# FMU_Power_FMU_REV_1A.net
KiCad netlist of a schematic drawn in Altium Designer
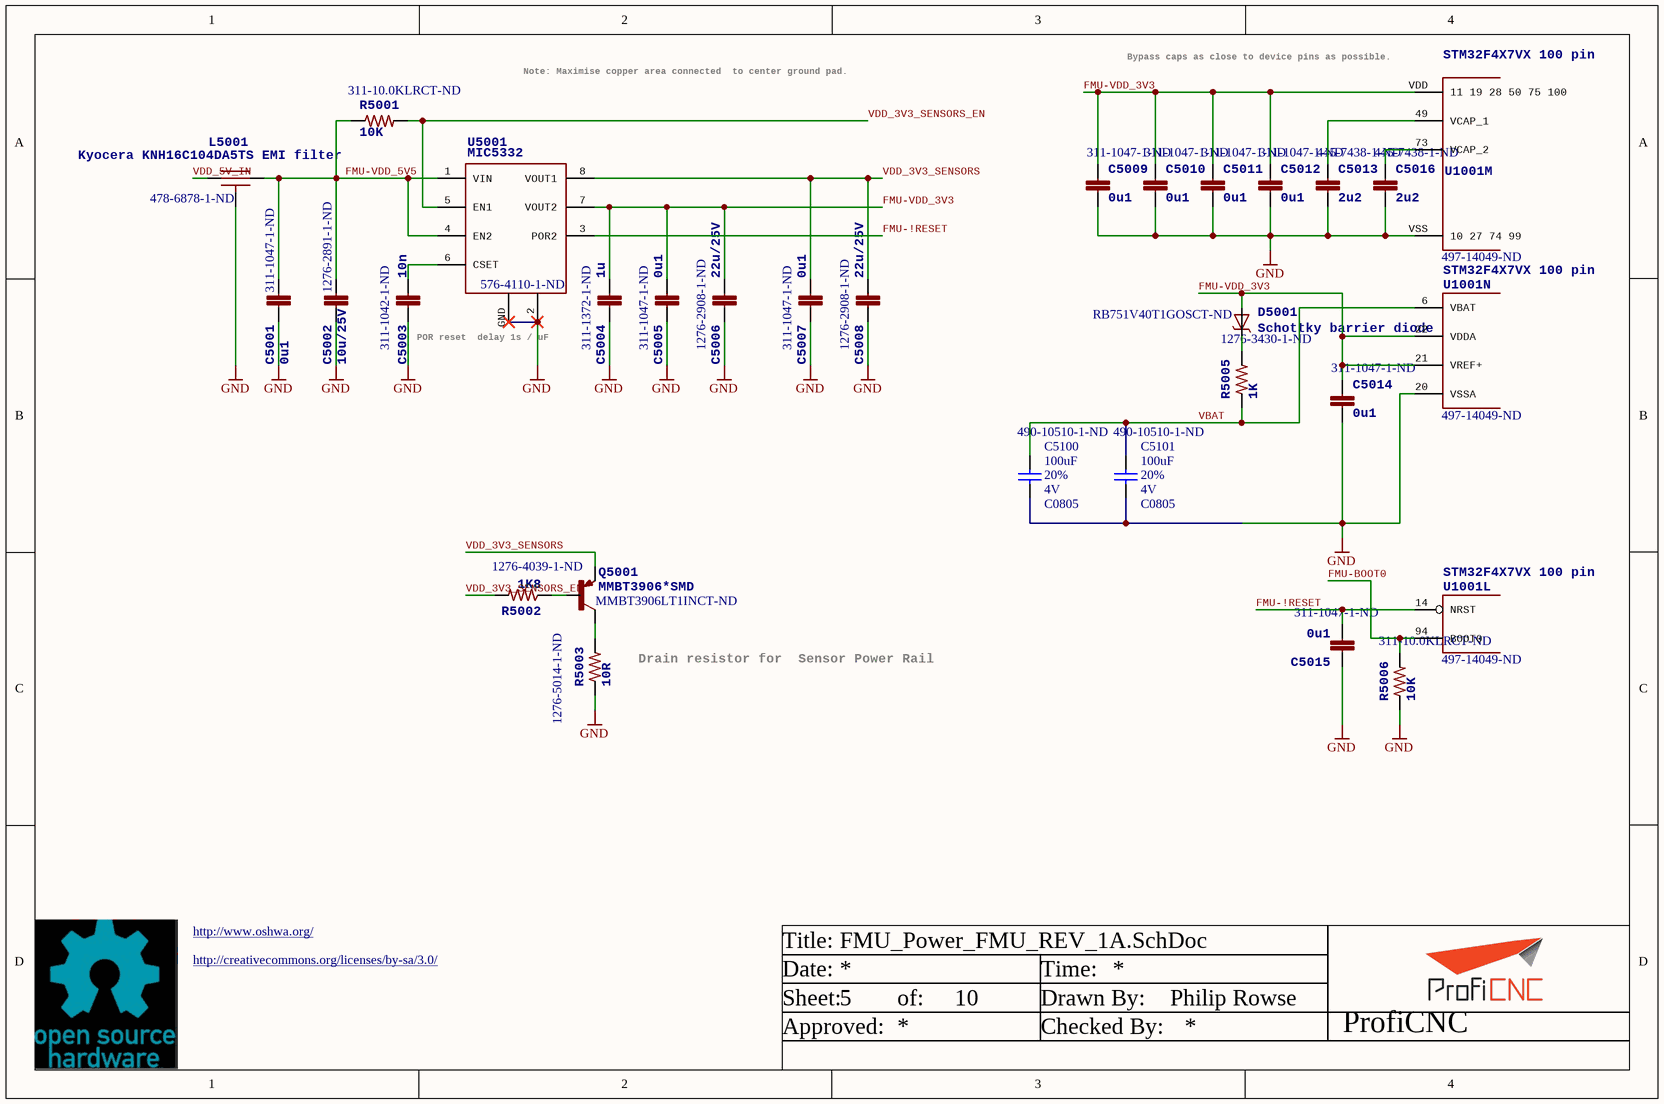
[diagram p0: FMU_Power_FMU_REV_1A.SchDoc]

(export (version "E")
  (design (tool "Eeschema 10.0.6"))
  (components
    (comp (ref "C5001")
      (value "0u1")
      (footprint "0402-CAP")
      (description "CAP CER 0.1UF 16V Y5V 0402")
      (fields
        (field (name "PARTNO") "CC0402ZRY5V7BB104")
        (field (name "SUPPLIER PART NUMBER 1") "311-1047-1-ND")
        (field (name "3DR_PARTNO") "ECM0700")
      )
      (libsource (lib "pixhawk2") (part "CAP0402"))
    )
    (comp (ref "C5002")
      (value "10u/25V")
      (footprint "0805-CAP")
      (description "CAP CER 10UF 25V 10% X5R 0805")
      (fields
        (field (name "PARTNO") "CL21A106KAYNNNE")
        (field (name "SUPPLIER PART NUMBER 1") "1276-2891-1-ND")
        (field (name "3DR_PARTNO") "ECM0714")
      )
      (libsource (lib "pixhawk2") (part "CAP0805"))
    )
    (comp (ref "C5003")
      (value "10n")
      (footprint "0402-CAP")
      (description "CAP CER 10000PF 16V 10% X7R 0402")
      (fields
        (field (name "PARTNO") "CC0402KRX7R7BB103")
        (field (name "SUPPLIER PART NUMBER 1") "311-1042-1-ND")
        (field (name "3DR_PARTNO") "ECM0711")
      )
      (libsource (lib "") (part "CAP0402_1"))
    )
    (comp (ref "C5004")
      (value "1u")
      (footprint "0603-CAP")
      (description "CAP CER 1UF 16V Y5V 0603")
      (fields
        (field (name "PARTNO") "CC0603ZRY5V7BB105")
        (field (name "SUPPLIER PART NUMBER 1") "311-1372-1-ND")
        (field (name "3DR_PARTNO") "ECM0705")
      )
      (libsource (lib "pixhawk2") (part "CAP0603"))
    )
    (comp (ref "C5005")
      (value "0u1")
      (footprint "0402-CAP")
      (description "CAP CER 0.1UF 16V Y5V 0402")
      (fields
        (field (name "PARTNO") "CC0402ZRY5V7BB104")
        (field (name "SUPPLIER PART NUMBER 1") "311-1047-1-ND")
        (field (name "3DR_PARTNO") "ECM0700")
      )
      (libsource (lib "pixhawk2") (part "CAP0402"))
    )
    (comp (ref "C5006")
      (value "22u/25V")
      (footprint "0805-CAP")
      (description "CAP CER 22UF 25V 20% X5R 0805")
      (fields
        (field (name "PARTNO") "CL21A226MAQNNNE")
        (field (name "SUPPLIER PART NUMBER 1") "1276-2908-1-ND")
        (field (name "3DR_PARTNO") "ECM0715")
      )
      (libsource (lib "pixhawk2") (part "CAP0805"))
    )
    (comp (ref "C5007")
      (value "0u1")
      (footprint "0402-CAP")
      (description "CAP CER 0.1UF 16V Y5V 0402")
      (fields
        (field (name "PARTNO") "CC0402ZRY5V7BB104")
        (field (name "SUPPLIER PART NUMBER 1") "311-1047-1-ND")
        (field (name "3DR_PARTNO") "ECM0700")
      )
      (libsource (lib "pixhawk2") (part "CAP0402"))
    )
    (comp (ref "C5008")
      (value "22u/25V")
      (footprint "0805-CAP")
      (description "CAP CER 22UF 25V 20% X5R 0805")
      (fields
        (field (name "PARTNO") "CL21A226MAQNNNE")
        (field (name "SUPPLIER PART NUMBER 1") "1276-2908-1-ND")
        (field (name "3DR_PARTNO") "ECM0715")
      )
      (libsource (lib "pixhawk2") (part "CAP0805"))
    )
    (comp (ref "C5009")
      (value "0u1")
      (footprint "0402-CAP")
      (description "CAP CER 0.1UF 16V Y5V 0402")
      (fields
        (field (name "PARTNO") "CC0402ZRY5V7BB104")
        (field (name "SUPPLIER PART NUMBER 1") "311-1047-1-ND")
        (field (name "3DR_PARTNO") "ECM0700")
      )
      (libsource (lib "pixhawk2") (part "CAP0402"))
    )
    (comp (ref "C5010")
      (value "0u1")
      (footprint "0402-CAP")
      (description "CAP CER 0.1UF 16V Y5V 0402")
      (fields
        (field (name "PARTNO") "CC0402ZRY5V7BB104")
        (field (name "SUPPLIER PART NUMBER 1") "311-1047-1-ND")
        (field (name "3DR_PARTNO") "ECM0700")
      )
      (libsource (lib "pixhawk2") (part "CAP0402"))
    )
    (comp (ref "C5011")
      (value "0u1")
      (footprint "0402-CAP")
      (description "CAP CER 0.1UF 16V Y5V 0402")
      (fields
        (field (name "PARTNO") "CC0402ZRY5V7BB104")
        (field (name "SUPPLIER PART NUMBER 1") "311-1047-1-ND")
        (field (name "3DR_PARTNO") "ECM0700")
      )
      (libsource (lib "pixhawk2") (part "CAP0402"))
    )
    (comp (ref "C5012")
      (value "0u1")
      (footprint "0402-CAP")
      (description "CAP CER 0.1UF 16V Y5V 0402")
      (fields
        (field (name "PARTNO") "CC0402ZRY5V7BB104")
        (field (name "SUPPLIER PART NUMBER 1") "311-1047-1-ND")
        (field (name "3DR_PARTNO") "ECM0700")
      )
      (libsource (lib "pixhawk2") (part "CAP0402"))
    )
    (comp (ref "C5013")
      (value "2u2")
      (footprint "0603-CAP")
      (description "CAP CER 2.2UF 16V 10% X6S 0603")
      (fields
        (field (name "PARTNO") "C1608X6S1C225K080AC")
        (field (name "SUPPLIER PART NUMBER 1") "445-7438-1-ND")
        (field (name "3DR_PARTNO") "ECM0619")
      )
      (libsource (lib "pixhawk2") (part "CAP0603"))
    )
    (comp (ref "C5014")
      (value "0u1")
      (footprint "0402-CAP")
      (description "CAP CER 0.1UF 16V Y5V 0402")
      (fields
        (field (name "PARTNO") "CC0402ZRY5V7BB104")
        (field (name "SUPPLIER PART NUMBER 1") "311-1047-1-ND")
        (field (name "3DR_PARTNO") "ECM0700")
      )
      (libsource (lib "pixhawk2") (part "CAP0402"))
    )
    (comp (ref "C5015")
      (value "0u1")
      (footprint "0402-CAP")
      (description "CAP CER 0.1UF 16V Y5V 0402")
      (fields
        (field (name "PARTNO") "CC0402ZRY5V7BB104")
        (field (name "SUPPLIER PART NUMBER 1") "311-1047-1-ND")
        (field (name "3DR_PARTNO") "ECM0700")
      )
      (libsource (lib "") (part "CAP0402_2"))
    )
    (comp (ref "C5016")
      (value "2u2")
      (footprint "0603-CAP")
      (description "CAP CER 2.2UF 16V 10% X6S 0603")
      (fields
        (field (name "PARTNO") "C1608X6S1C225K080AC")
        (field (name "SUPPLIER PART NUMBER 1") "445-7438-1-ND")
        (field (name "3DR_PARTNO") "ECM0619")
      )
      (libsource (lib "pixhawk2") (part "CAP0603"))
    )
    (comp (ref "C5100")
      (value "100uF")
      (footprint "C0805")
      (fields
        (field (name "TOLERANCE") "20%")
        (field (name "VOLTAGE") "4V")
        (field (name "SUPPLIER PART NUMBER 1") "490-10510-1-ND")
        (field (name "Comment") "GRM21BR60G107ME15L")
      )
      (libsource (lib "3DR") (part "Capacitor"))
    )
    (comp (ref "C5101")
      (value "100uF")
      (footprint "C0805")
      (fields
        (field (name "TOLERANCE") "20%")
        (field (name "VOLTAGE") "4V")
        (field (name "SUPPLIER PART NUMBER 1") "490-10510-1-ND")
        (field (name "Comment") "GRM21BR60G107ME15L")
      )
      (libsource (lib "3DR") (part "Capacitor"))
    )
    (comp (ref "D5001")
      (value "Schottky barrier diode")
      (footprint "SOD323")
      (description "DIODE SCHOTTKY 30V 0.03A SOD323")
      (fields
        (field (name "SUPPLIER PART NUMBER 1") "RB751V40T1GOSCT-ND")
        (field (name "3DR_PARTNO") "ECM0839")
        (field (name "PARTNO") "RB751V40T1G")
      )
      (libsource (lib "pixhawk2") (part "DIODE-SCHOTTKY_SOD323"))
    )
    (comp (ref "L5001")
      (value "Kyocera KNH16C104DA5TS EMI filter")
      (footprint "KYOCERA-KNH16-DA")
      (description "FILTER CAP 0.1UF 2A 25V 0603")
      (fields
        (field (name "SUPPLIER PART NUMBER 1") "478-6878-1-ND")
        (field (name "3DR_PARTNO") "ECM0719")
        (field (name "PARTNO") "KNH16C104DA5TS")
      )
      (libsource (lib "pixhawk2") (part "KNH16C104DA5TS"))
    )
    (comp (ref "Q5001")
      (value "MMBT3906*SMD")
      (footprint "SOT23-BEC")
      (description "TRANSISTOR SWITCHING PNP SOT-23")
      (fields
        (field (name "SUPPLIER PART NUMBER 1") "MMBT3906LT1INCT-ND")
        (field (name "3DR_PARTNO") "ECM0833")
        (field (name "PARTNO") "MMBT 3906 LT1")
      )
      (libsource (lib "transistor-pnp") (part "MMBT3906*SMD"))
    )
    (comp (ref "R5001")
      (value "10K")
      (footprint "0402-RES")
      (description "RES 10K OHM 1/16W 1% 0402 SMD")
      (fields
        (field (name "PARTNO") "RC0402FR-0710KL")
        (field (name "SUPPLIER PART NUMBER 1") "311-10.0KLRCT-ND")
        (field (name "3DR_PARTNO") "ECM0800")
      )
      (libsource (lib "pixhawk2") (part "RESISTOR0402-RES"))
    )
    (comp (ref "R5002")
      (value "1K8")
      (footprint "0402-RES")
      (description "RES 1.8K OHM 1/16W 1% 0402")
      (fields
        (field (name "PARTNO") "RC1005F182CS")
        (field (name "SUPPLIER PART NUMBER 1") "1276-4039-1-ND")
        (field (name "3DR_PARTNO") "ECM0807")
      )
      (libsource (lib "pixhawk2") (part "RESISTOR0402-RES"))
    )
    (comp (ref "R5003")
      (value "10R")
      (footprint "0603-RES")
      (description "RES 10 OHM 1/10W 5% 0603")
      (fields
        (field (name "PARTNO") "RC1608J100CS")
        (field (name "SUPPLIER PART NUMBER 1") "1276-5014-1-ND")
        (field (name "3DR_PARTNO") "ECM0811")
      )
      (libsource (lib "pixhawk2") (part "RESISTOR0603-RES"))
    )
    (comp (ref "R5005")
      (value "1K")
      (footprint "0402-RES")
      (description "RES 1K OHM 1/16W 1% 0402")
      (fields
        (field (name "PARTNO") "RC1005F102CS")
        (field (name "SUPPLIER PART NUMBER 1") "1276-3430-1-ND")
        (field (name "3DR_PARTNO") "ECM0804")
      )
      (libsource (lib "pixhawk2") (part "RESISTOR0402-RES"))
    )
    (comp (ref "R5006")
      (value "10K")
      (footprint "0402-RES")
      (description "RES 10K OHM 1/16W 1% 0402 SMD")
      (fields
        (field (name "PARTNO") "RC0402FR-0710KL")
        (field (name "SUPPLIER PART NUMBER 1") "311-10.0KLRCT-ND")
        (field (name "3DR_PARTNO") "ECM0800")
      )
      (libsource (lib "pixhawk2") (part "RESISTOR0402-RES"))
    )
    (comp (ref "U1001")
      (value "STM32F4X7VX 100 pin")
      (footprint "TQFP100")
      (description "REV 3 Silicon or later IC MCU ARM 2MB FLASH 100LQFP")
      (fields (field (name "SUPPLIER PART NUMBER 1") "497-14049-ND") (field (name "3DR_PARTNO") "ECM0841"))
      (libsource (lib "pixhawk2") (part "STM32F4X7VX"))
    )
    (comp (ref "U5001")
      (value "MIC5332")
      (footprint "MLF-8-EPAD")
      (description "IC REG LDO 3.3V 0.3A 8TMLF")
      (fields
        (field (name "SUPPLIER PART NUMBER 1") "576-4110-1-ND")
        (field (name "3DR_PARTNO") "ECM0832")
        (field (name "PARTNO") "MIC5332-SSYMT TR")
      )
      (libsource (lib "pixhawk2") (part "MIC5332"))
    )
  )
  (nets
    (net (code "1") (name "/FMU-!RESET") (class "Default")
      (node (ref "C5015") (pin "P$2") (pinfunction "2_P$2") (pintype "passive"))
      (node (ref "U1001") (pin "14") (pinfunction "NRST_14") (pintype "passive"))
      (node (ref "U5001") (pin "3") (pinfunction "POR2_3") (pintype "passive"))
    )
    (net (code "2") (name "/FMU-BOOT0") (class "Default")
      (node (ref "R5006") (pin "P$2") (pinfunction "2_P$2") (pintype "passive"))
      (node (ref "U1001") (pin "94") (pinfunction "BOOT0_94") (pintype "passive"))
    )
    (net (code "3") (name "/FMU-VDD_3V3") (class "Default")
      (node (ref "C5004") (pin "P$1") (pinfunction "1_P$1") (pintype "passive"))
      (node (ref "C5005") (pin "P$1") (pinfunction "1_P$1") (pintype "passive"))
      (node (ref "C5006") (pin "P$1") (pinfunction "1_P$1") (pintype "passive"))
      (node (ref "C5009") (pin "P$1") (pinfunction "1_P$1") (pintype "passive"))
      (node (ref "C5010") (pin "P$1") (pinfunction "1_P$1") (pintype "passive"))
      (node (ref "C5011") (pin "P$1") (pinfunction "1_P$1") (pintype "passive"))
      (node (ref "C5012") (pin "P$1") (pinfunction "1_P$1") (pintype "passive"))
      (node (ref "C5014") (pin "P$1") (pinfunction "1_P$1") (pintype "passive"))
      (node (ref "D5001") (pin "A") (pinfunction "A_A") (pintype "passive"))
      (node (ref "U1001") (pin "21") (pinfunction "VREF+_21") (pintype "passive"))
      (node (ref "U1001") (pin "22") (pinfunction "VDDA_22") (pintype "power_in"))
      (node (ref "U1001") (pin "VDD") (pinfunction "11_19_28_50_75_100_VDD") (pintype "power_in"))
      (node (ref "U5001") (pin "7") (pinfunction "VOUT2_7") (pintype "passive"))
    )
    (net (code "4") (name "/FMU-VDD_5V5") (class "Default")
      (node (ref "C5001") (pin "P$1") (pinfunction "1_P$1") (pintype "passive"))
      (node (ref "C5002") (pin "P$1") (pinfunction "1_P$1") (pintype "passive"))
      (node (ref "L5001") (pin "P$2") (pinfunction "P$2_P$2") (pintype "passive"))
      (node (ref "R5001") (pin "P$1") (pinfunction "1_P$1") (pintype "passive"))
      (node (ref "U5001") (pin "1") (pinfunction "VIN_1") (pintype "passive"))
      (node (ref "U5001") (pin "4") (pinfunction "EN2_4") (pintype "passive"))
    )
    (net (code "5") (name "/VBAT") (class "Default")
      (node (ref "C5100") (pin "2") (pinfunction "2_2") (pintype "passive"))
      (node (ref "C5101") (pin "2") (pinfunction "2_2") (pintype "passive"))
      (node (ref "R5005") (pin "P$1") (pinfunction "1_P$1") (pintype "passive"))
      (node (ref "U1001") (pin "6") (pinfunction "VBAT_6") (pintype "power_in"))
    )
    (net (code "6") (name "/VDD_3V3_SENSORS") (class "Default")
      (node (ref "C5007") (pin "P$1") (pinfunction "1_P$1") (pintype "passive"))
      (node (ref "C5008") (pin "P$1") (pinfunction "1_P$1") (pintype "passive"))
      (node (ref "Q5001") (pin "E") (pinfunction "E_E") (pintype "passive"))
      (node (ref "U5001") (pin "8") (pinfunction "VOUT1_8") (pintype "passive"))
    )
    (net (code "7") (name "/VDD_3V3_SENSORS_EN") (class "Default")
      (node (ref "R5001") (pin "P$2") (pinfunction "2_P$2") (pintype "passive"))
      (node (ref "R5002") (pin "P$2") (pinfunction "2_P$2") (pintype "passive"))
      (node (ref "U5001") (pin "5") (pinfunction "EN1_5") (pintype "passive"))
    )
    (net (code "8") (name "/VDD_5V_IN") (class "Default")
      (node (ref "L5001") (pin "P$1") (pinfunction "P$1_P$1") (pintype "passive"))
    )
    (net (code "9") (name "GND") (class "Default")
      (node (ref "C5001") (pin "P$2") (pinfunction "2_P$2") (pintype "passive"))
      (node (ref "C5002") (pin "P$2") (pinfunction "2_P$2") (pintype "passive"))
      (node (ref "C5003") (pin "P$1") (pinfunction "1_P$1") (pintype "passive"))
      (node (ref "C5004") (pin "P$2") (pinfunction "2_P$2") (pintype "passive"))
      (node (ref "C5005") (pin "P$2") (pinfunction "2_P$2") (pintype "passive"))
      (node (ref "C5006") (pin "P$2") (pinfunction "2_P$2") (pintype "passive"))
      (node (ref "C5007") (pin "P$2") (pinfunction "2_P$2") (pintype "passive"))
      (node (ref "C5008") (pin "P$2") (pinfunction "2_P$2") (pintype "passive"))
      (node (ref "C5009") (pin "P$2") (pinfunction "2_P$2") (pintype "passive"))
      (node (ref "C5010") (pin "P$2") (pinfunction "2_P$2") (pintype "passive"))
      (node (ref "C5011") (pin "P$2") (pinfunction "2_P$2") (pintype "passive"))
      (node (ref "C5012") (pin "P$2") (pinfunction "2_P$2") (pintype "passive"))
      (node (ref "C5013") (pin "P$2") (pinfunction "2_P$2") (pintype "passive"))
      (node (ref "C5014") (pin "P$2") (pinfunction "2_P$2") (pintype "passive"))
      (node (ref "C5015") (pin "P$1") (pinfunction "1_P$1") (pintype "passive"))
      (node (ref "C5016") (pin "P$2") (pinfunction "2_P$2") (pintype "passive"))
      (node (ref "C5100") (pin "1") (pinfunction "1_1") (pintype "passive"))
      (node (ref "C5101") (pin "1") (pinfunction "1_1") (pintype "passive"))
      (node (ref "L5001") (pin "GND") (pinfunction "GND_GND") (pintype "passive"))
      (node (ref "R5003") (pin "1") (pinfunction "1_1") (pintype "passive"))
      (node (ref "R5006") (pin "P$1") (pinfunction "1_P$1") (pintype "passive"))
      (node (ref "U1001") (pin "20") (pinfunction "VSSA_20") (pintype "power_in"))
      (node (ref "U1001") (pin "VSS") (pinfunction "10_27_74_99_VSS") (pintype "power_in"))
      (node (ref "U5001") (pin "2") (pinfunction "GND_2") (pintype "power_in"))
      (node (ref "U5001") (pin "GND") (pinfunction "GND_GND") (pintype "power_in"))
    )
    (net (code "10") (name "Net-(C5003-2)") (class "Default")
      (node (ref "C5003") (pin "P$2") (pinfunction "2_P$2") (pintype "passive"))
      (node (ref "U5001") (pin "6") (pinfunction "CSET_6") (pintype "passive"))
    )
    (net (code "11") (name "Net-(C5013-1)") (class "Default")
      (node (ref "C5013") (pin "P$1") (pinfunction "1_P$1") (pintype "passive"))
      (node (ref "U1001") (pin "49") (pinfunction "VCAP_1_49") (pintype "power_in"))
    )
    (net (code "12") (name "Net-(C5016-1)") (class "Default")
      (node (ref "C5016") (pin "P$1") (pinfunction "1_P$1") (pintype "passive"))
      (node (ref "U1001") (pin "73") (pinfunction "VCAP_2_73") (pintype "power_in"))
    )
    (net (code "13") (name "Net-(Q5001-PadC)") (class "Default")
      (node (ref "Q5001") (pin "C") (pinfunction "C_C") (pintype "passive"))
      (node (ref "R5003") (pin "2") (pinfunction "2_2") (pintype "passive"))
    )
    (net (code "14") (name "Net-(R5002-1)") (class "Default")
      (node (ref "Q5001") (pin "B") (pinfunction "B_B") (pintype "passive"))
      (node (ref "R5002") (pin "P$1") (pinfunction "1_P$1") (pintype "passive"))
    )
    (net (code "15") (name "Net-(R5005-2)") (class "Default")
      (node (ref "D5001") (pin "C") (pinfunction "C_C") (pintype "passive"))
      (node (ref "R5005") (pin "P$2") (pinfunction "2_P$2") (pintype "passive"))
    )
  )
)
